# ModuleCarrier-NINA-B1-v1_0_0.net
KiCad netlist of a schematic drawn in EAGLE
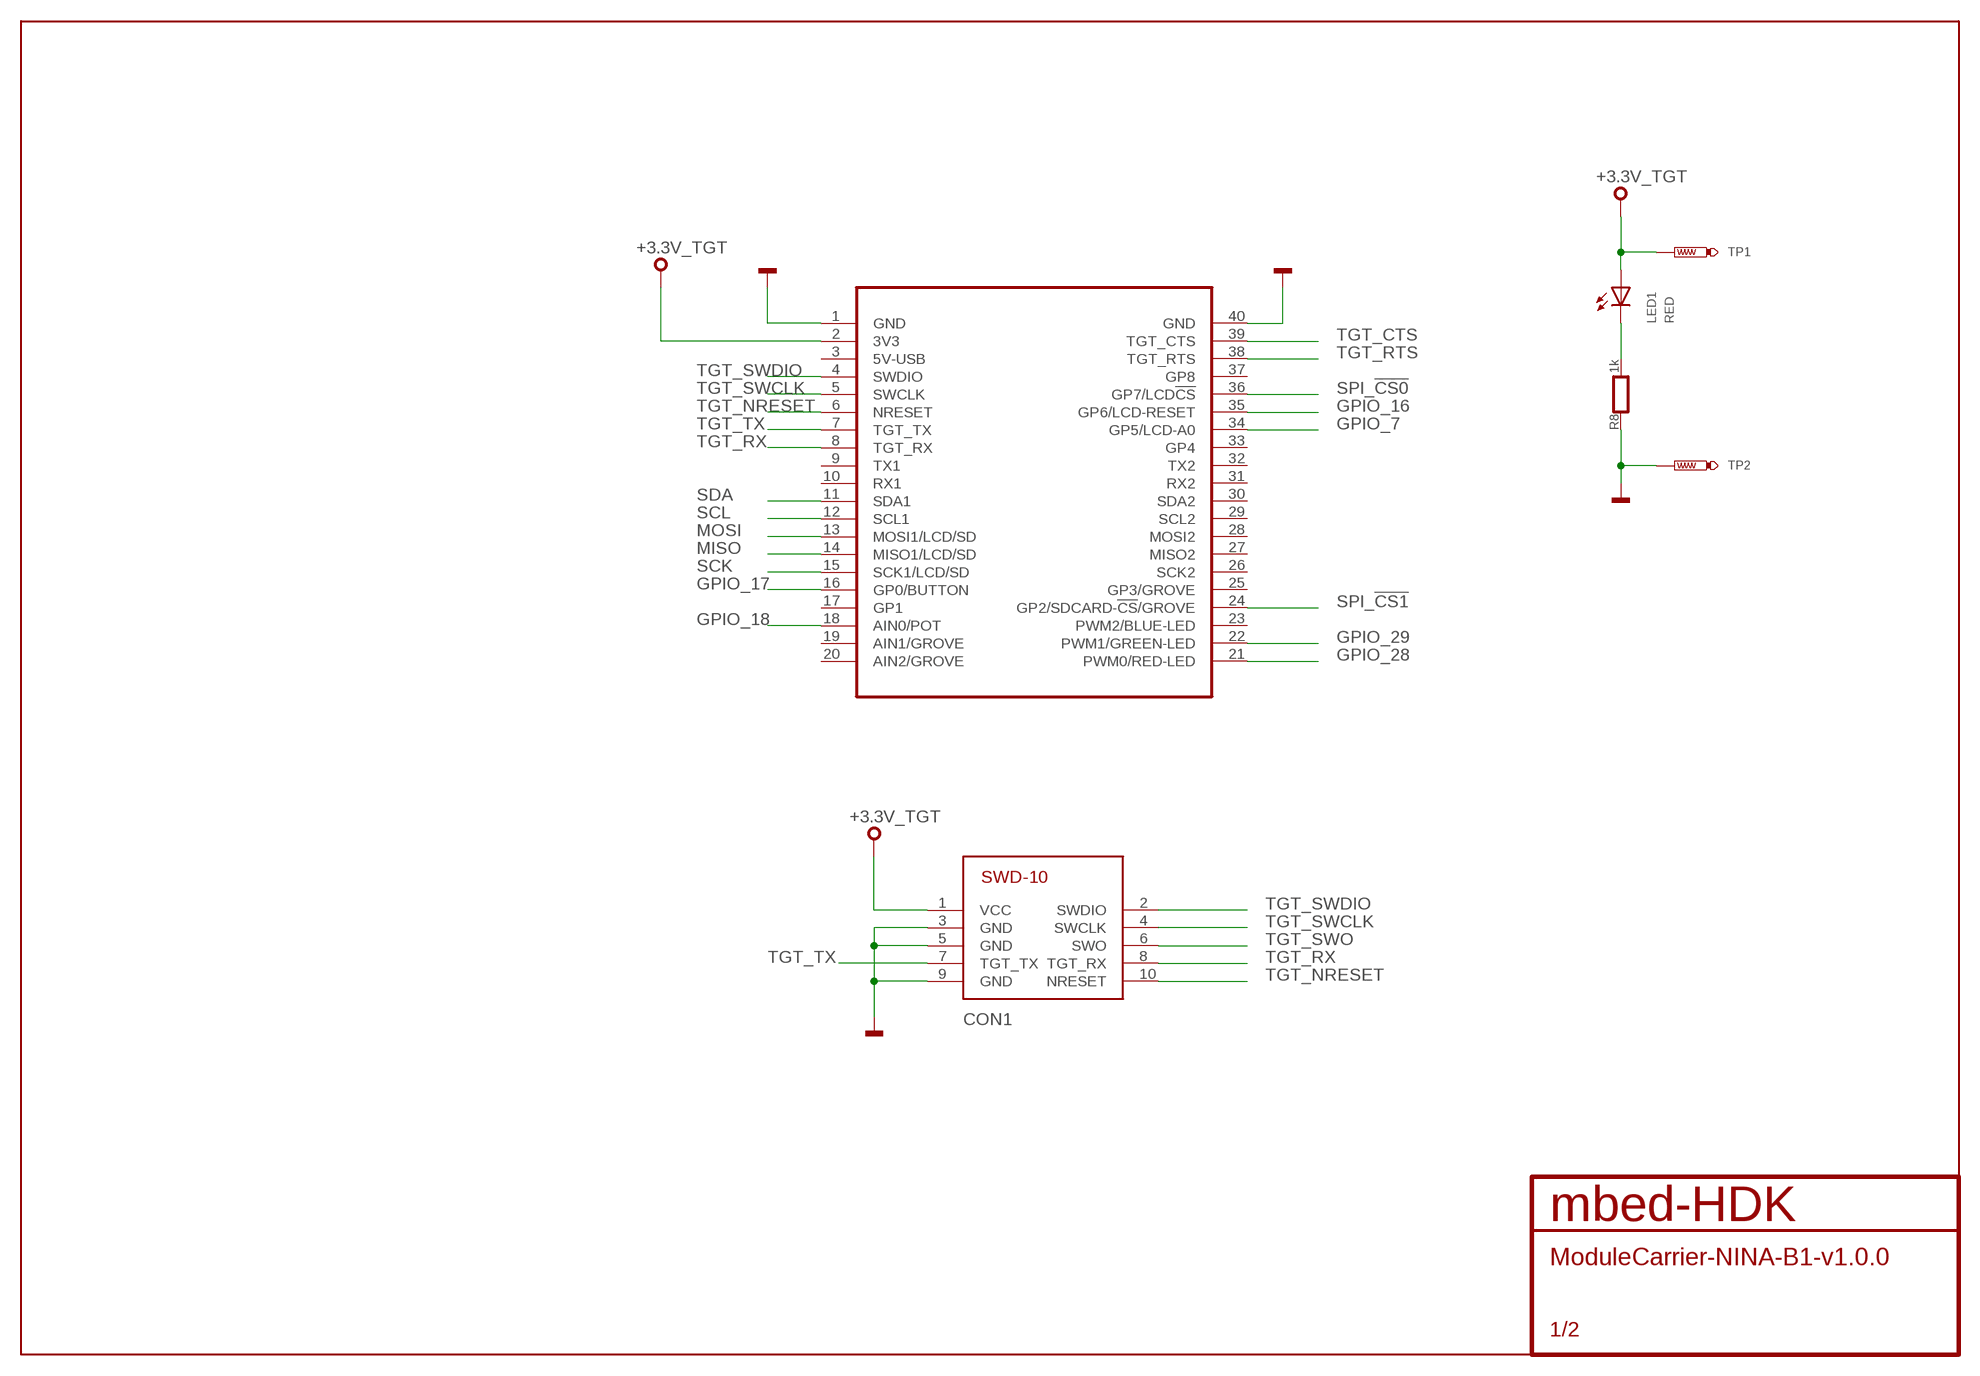
[diagram p0: schematic, sheet 1]
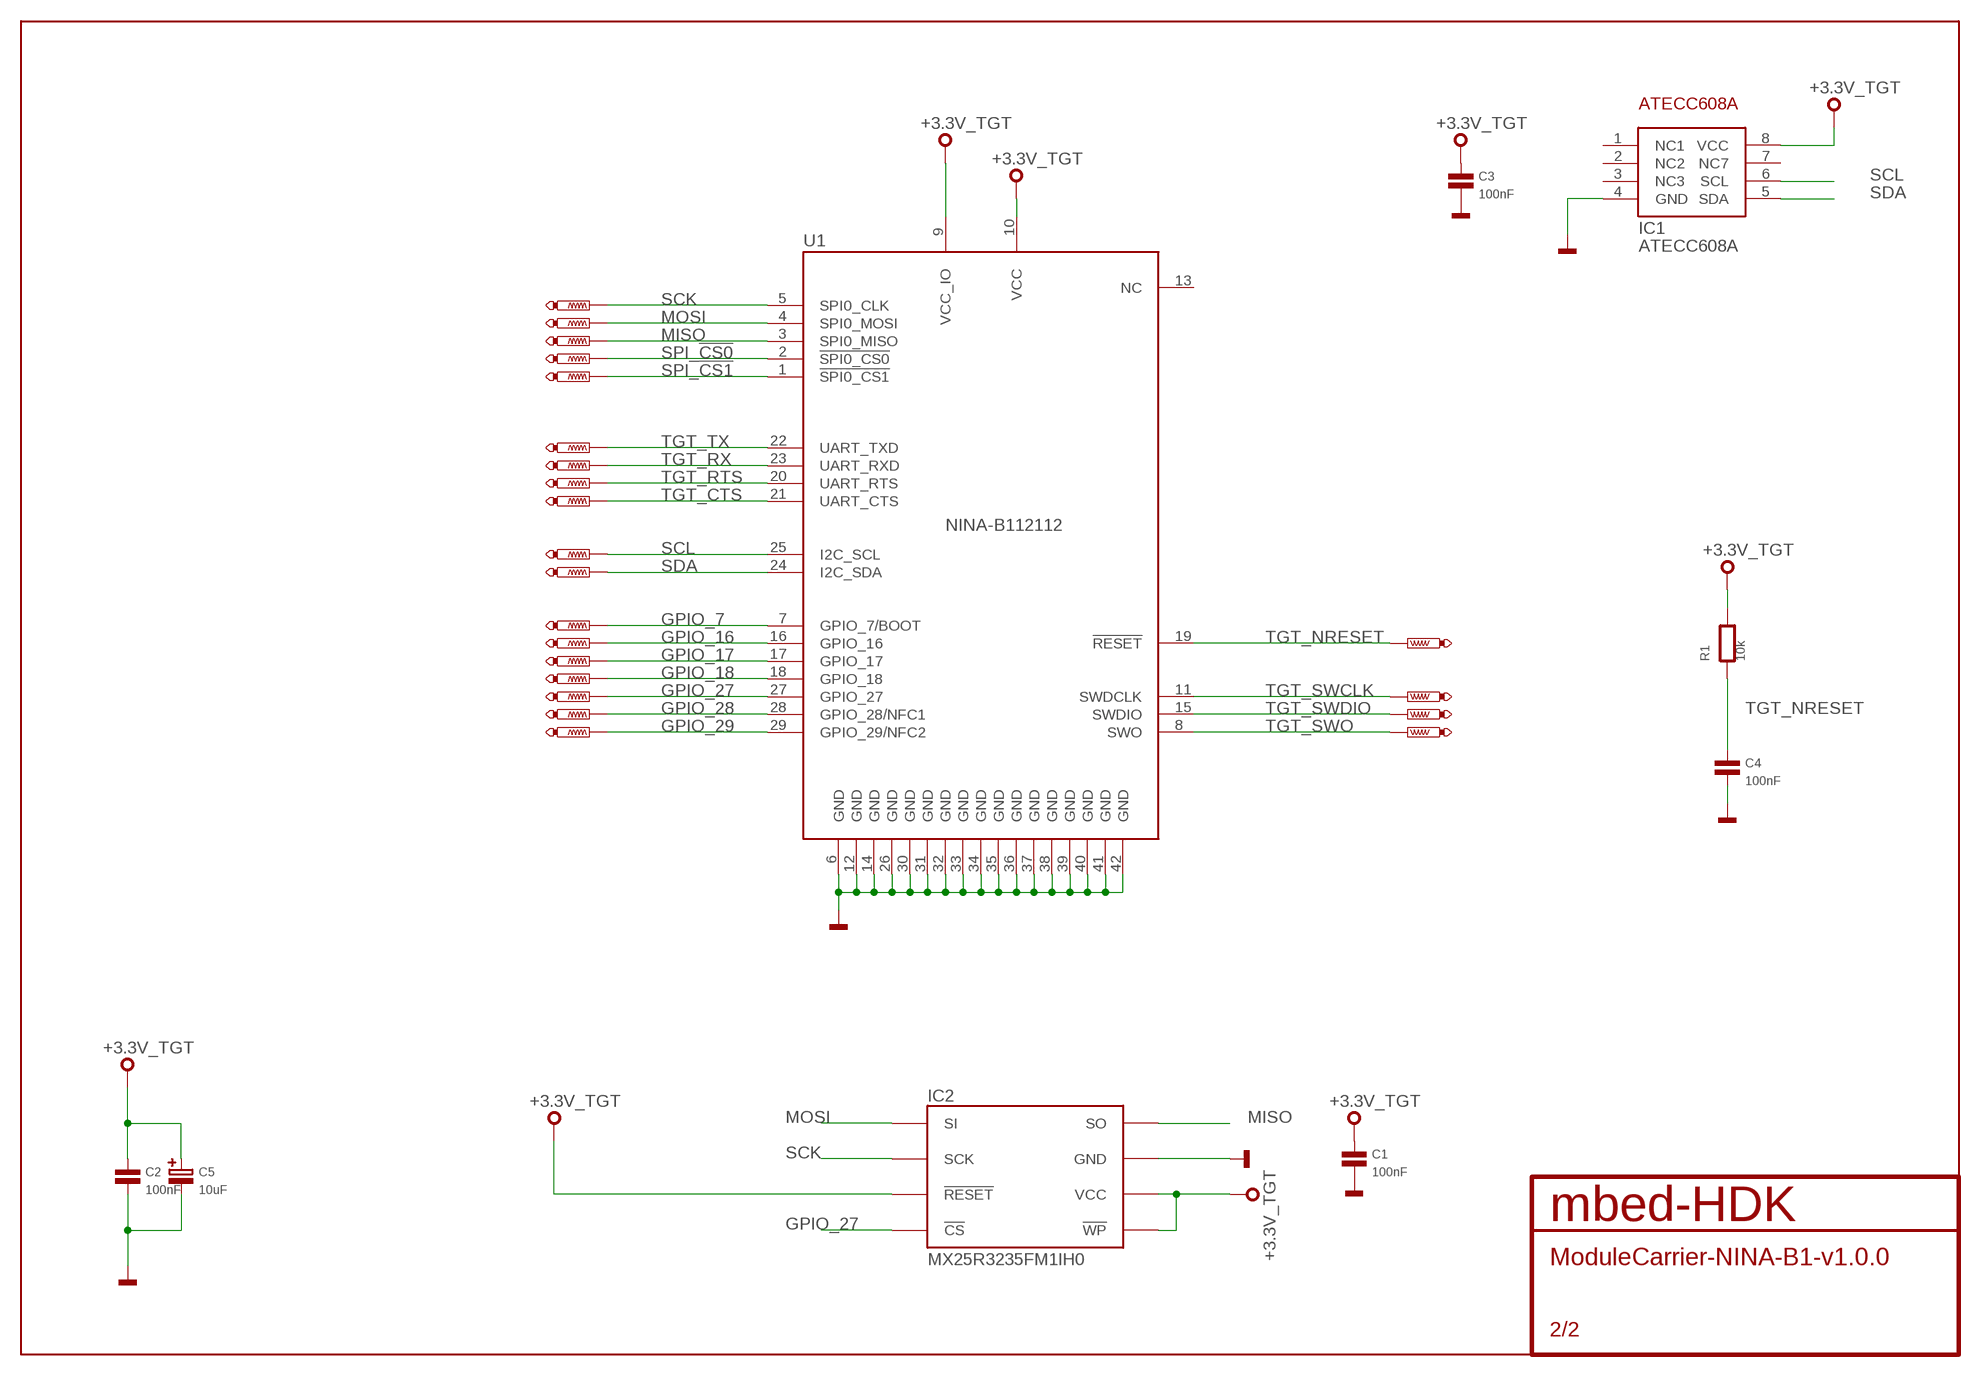
[diagram p1: schematic, sheet 2]

(export (version "E")
  (design (tool "Eeschema 10.0.6"))
  (components
    (comp (ref "C1")
      (value "100nF")
      (footprint "eagle-import:0603")
      (libsource (lib "eagle-import") (part "CAPACITOR0603"))
    )
    (comp (ref "C2")
      (value "100nF")
      (footprint "eagle-import:0603")
      (libsource (lib "eagle-import") (part "CAPACITOR0603"))
    )
    (comp (ref "C3")
      (value "100nF")
      (footprint "eagle-import:0603")
      (libsource (lib "eagle-import") (part "CAPACITOR0603"))
    )
    (comp (ref "C4")
      (value "100nF")
      (footprint "eagle-import:0603")
      (libsource (lib "eagle-import") (part "CAPACITOR0603"))
    )
    (comp (ref "C5")
      (value "10uF")
      (footprint "eagle-import:SMC_B")
      (fields (field (name "MF") "Kemet"))
      (libsource (lib "eagle-import") (part "CAPACITOR-POLARISEDB"))
    )
    (comp (ref "IC1")
      (value "ATECC608A")
      (footprint "eagle-import:SO8")
      (libsource (lib "eagle-import") (part "ATECC608A"))
    )
    (comp (ref "IC2")
      (value "MX25R3235FM1IH0")
      (footprint "eagle-import:SO8")
      (fields (field (name "MF") "Macronix"))
      (libsource (lib "eagle-import") (part "MX25R3235FM1IH0"))
    )
    (comp (ref "R1")
      (value "10k")
      (footprint "eagle-import:0603")
      (libsource (lib "eagle-import") (part "RESISTOR0603"))
    )
    (comp (ref "TP3")
      (value "PTR1B1,27")
      (footprint "eagle-import:B1,27")
      (libsource (lib "eagle-import") (part "PTR1B1,27"))
    )
    (comp (ref "TP4")
      (value "PTR1B1,27")
      (footprint "eagle-import:B1,27")
      (libsource (lib "eagle-import") (part "PTR1B1,27"))
    )
    (comp (ref "TP5")
      (value "PTR1B1,27")
      (footprint "eagle-import:B1,27")
      (libsource (lib "eagle-import") (part "PTR1B1,27"))
    )
    (comp (ref "TP6")
      (value "PTR1B1,27")
      (footprint "eagle-import:B1,27")
      (libsource (lib "eagle-import") (part "PTR1B1,27"))
    )
    (comp (ref "TP7")
      (value "PTR1B1,27")
      (footprint "eagle-import:B1,27")
      (libsource (lib "eagle-import") (part "PTR1B1,27"))
    )
    (comp (ref "TP8")
      (value "PTR1B1,27")
      (footprint "eagle-import:B1,27")
      (libsource (lib "eagle-import") (part "PTR1B1,27"))
    )
    (comp (ref "TP9")
      (value "PTR1B1,27")
      (footprint "eagle-import:B1,27")
      (libsource (lib "eagle-import") (part "PTR1B1,27"))
    )
    (comp (ref "TP10")
      (value "PTR1B1,27")
      (footprint "eagle-import:B1,27")
      (libsource (lib "eagle-import") (part "PTR1B1,27"))
    )
    (comp (ref "TP11")
      (value "PTR1B1,27")
      (footprint "eagle-import:B1,27")
      (libsource (lib "eagle-import") (part "PTR1B1,27"))
    )
    (comp (ref "TP12")
      (value "PTR1B1,27")
      (footprint "eagle-import:B1,27")
      (libsource (lib "eagle-import") (part "PTR1B1,27"))
    )
    (comp (ref "TP13")
      (value "PTR1B1,27")
      (footprint "eagle-import:B1,27")
      (libsource (lib "eagle-import") (part "PTR1B1,27"))
    )
    (comp (ref "TP14")
      (value "PTR1B1,27")
      (footprint "eagle-import:B1,27")
      (libsource (lib "eagle-import") (part "PTR1B1,27"))
    )
    (comp (ref "TP15")
      (value "PTR1B1,27")
      (footprint "eagle-import:B1,27")
      (libsource (lib "eagle-import") (part "PTR1B1,27"))
    )
    (comp (ref "TP16")
      (value "PTR1B1,27")
      (footprint "eagle-import:B1,27")
      (libsource (lib "eagle-import") (part "PTR1B1,27"))
    )
    (comp (ref "TP17")
      (value "PTR1B1,27")
      (footprint "eagle-import:B1,27")
      (libsource (lib "eagle-import") (part "PTR1B1,27"))
    )
    (comp (ref "TP18")
      (value "PTR1B1,27")
      (footprint "eagle-import:B1,27")
      (libsource (lib "eagle-import") (part "PTR1B1,27"))
    )
    (comp (ref "TP19")
      (value "PTR1B1,27")
      (footprint "eagle-import:B1,27")
      (libsource (lib "eagle-import") (part "PTR1B1,27"))
    )
    (comp (ref "TP20")
      (value "PTR1B1,27")
      (footprint "eagle-import:B1,27")
      (libsource (lib "eagle-import") (part "PTR1B1,27"))
    )
    (comp (ref "TP21")
      (value "PTR1B1,27")
      (footprint "eagle-import:B1,27")
      (libsource (lib "eagle-import") (part "PTR1B1,27"))
    )
    (comp (ref "TP22")
      (value "PTR1B1,27")
      (footprint "eagle-import:B1,27")
      (libsource (lib "eagle-import") (part "PTR1B1,27"))
    )
    (comp (ref "TP23")
      (value "PTR1B1,27")
      (footprint "eagle-import:B1,27")
      (libsource (lib "eagle-import") (part "PTR1B1,27"))
    )
    (comp (ref "TP24")
      (value "PTR1B1,27")
      (footprint "eagle-import:B1,27")
      (libsource (lib "eagle-import") (part "PTR1B1,27"))
    )
    (comp (ref "U1")
      (value "NINA-B112112")
      (footprint "eagle-import:NINA112-42")
      (libsource (lib "eagle-import") (part "NINA-B112112"))
    )
    (comp (ref "CON1")
      (value "SWD-10/TC2050_SMD")
      (footprint "eagle-import:FTSH-105-02")
      (libsource (lib "eagle-import") (part "SWD-10/TC2050_SMD"))
    )
    (comp (ref "LED1")
      (value "RED")
      (footprint "eagle-import:CHIPLED_0603")
      (fields (field (name "MF") "Wurth Electronics Inc"))
      (libsource (lib "eagle-import") (part "SMD_LED0603"))
    )
    (comp (ref "MOD1")
      (value "MODULE_DAUGHTER")
      (footprint "eagle-import:MODULE_DAUGHTER")
      (libsource (lib "eagle-import") (part "MODULE_DAUGHTER"))
    )
    (comp (ref "R8")
      (value "1k")
      (footprint "eagle-import:0603")
      (libsource (lib "eagle-import") (part "RESISTOR0603"))
    )
    (comp (ref "TP1")
      (value "TEST-POINT-50R-PTH")
      (footprint "eagle-import:TP50-PTH")
      (libsource (lib "eagle-import") (part "TEST-POINT-50R-PTH"))
    )
    (comp (ref "TP2")
      (value "TEST-POINT-50R-PTH")
      (footprint "eagle-import:TP50-PTH")
      (libsource (lib "eagle-import") (part "TEST-POINT-50R-PTH"))
    )
  )
  (nets
    (net (code "1") (name "+3.3V_TGT") (class "Default")
      (node (ref "C1") (pin "1") (pinfunction "P$1_1") (pintype "passive"))
      (node (ref "C2") (pin "1") (pinfunction "P$1_1") (pintype "passive"))
      (node (ref "C3") (pin "1") (pinfunction "P$1_1") (pintype "passive"))
      (node (ref "C5") (pin "+") (pinfunction "+_+") (pintype "passive"))
      (node (ref "CON1") (pin "1") (pinfunction "VCC_1") (pintype "bidirectional"))
      (node (ref "IC1") (pin "8") (pinfunction "VCC_8") (pintype "bidirectional"))
      (node (ref "IC2") (pin "3") (pinfunction "~{WP}_3") (pintype "bidirectional"))
      (node (ref "IC2") (pin "7") (pinfunction "~{RESET}_7") (pintype "bidirectional"))
      (node (ref "IC2") (pin "8") (pinfunction "VCC_8") (pintype "bidirectional"))
      (node (ref "LED1") (pin "A") (pinfunction "A_A") (pintype "passive"))
      (node (ref "MOD1") (pin "2") (pinfunction "3V3_2") (pintype "bidirectional"))
      (node (ref "R1") (pin "2") (pinfunction "P$2_2") (pintype "passive"))
      (node (ref "TP1") (pin "TP") (pinfunction "TP_TP") (pintype "input"))
      (node (ref "U1") (pin "10") (pinfunction "VCC_10") (pintype "power_in"))
      (node (ref "U1") (pin "9") (pinfunction "VCC_IO_9") (pintype "power_in"))
    )
    (net (code "2") (name "GND") (class "Default")
      (node (ref "C1") (pin "2") (pinfunction "P$2_2") (pintype "passive"))
      (node (ref "C2") (pin "2") (pinfunction "P$2_2") (pintype "passive"))
      (node (ref "C3") (pin "2") (pinfunction "P$2_2") (pintype "passive"))
      (node (ref "C4") (pin "2") (pinfunction "P$2_2") (pintype "passive"))
      (node (ref "C5") (pin "-") (pinfunction "-_-") (pintype "passive"))
      (node (ref "CON1") (pin "3") (pinfunction "GND_3") (pintype "bidirectional"))
      (node (ref "CON1") (pin "5") (pinfunction "GND_5") (pintype "bidirectional"))
      (node (ref "CON1") (pin "9") (pinfunction "GND_9") (pintype "bidirectional"))
      (node (ref "IC1") (pin "4") (pinfunction "GND_4") (pintype "bidirectional"))
      (node (ref "IC2") (pin "4") (pinfunction "GND_4") (pintype "bidirectional"))
      (node (ref "MOD1") (pin "1") (pinfunction "GND_1") (pintype "bidirectional"))
      (node (ref "MOD1") (pin "40") (pinfunction "GND_40") (pintype "bidirectional"))
      (node (ref "R8") (pin "1") (pinfunction "P$1_1") (pintype "passive"))
      (node (ref "TP2") (pin "TP") (pinfunction "TP_TP") (pintype "input"))
      (node (ref "U1") (pin "12") (pinfunction "GND_12") (pintype "power_in"))
      (node (ref "U1") (pin "14") (pinfunction "GND_14") (pintype "power_in"))
      (node (ref "U1") (pin "26") (pinfunction "GND_26") (pintype "power_in"))
      (node (ref "U1") (pin "30") (pinfunction "GND_30") (pintype "power_in"))
      (node (ref "U1") (pin "31") (pinfunction "GND_31") (pintype "power_in"))
      (node (ref "U1") (pin "32") (pinfunction "GND_32") (pintype "power_in"))
      (node (ref "U1") (pin "33") (pinfunction "GND_33") (pintype "power_in"))
      (node (ref "U1") (pin "34") (pinfunction "GND_34") (pintype "power_in"))
      (node (ref "U1") (pin "35") (pinfunction "GND_35") (pintype "power_in"))
      (node (ref "U1") (pin "36") (pinfunction "GND_36") (pintype "power_in"))
      (node (ref "U1") (pin "37") (pinfunction "GND_37") (pintype "power_in"))
      (node (ref "U1") (pin "38") (pinfunction "GND_38") (pintype "power_in"))
      (node (ref "U1") (pin "39") (pinfunction "GND_39") (pintype "power_in"))
      (node (ref "U1") (pin "40") (pinfunction "GND_40") (pintype "power_in"))
      (node (ref "U1") (pin "41") (pinfunction "GND_41") (pintype "power_in"))
      (node (ref "U1") (pin "42") (pinfunction "GND_42") (pintype "power_in"))
      (node (ref "U1") (pin "6") (pinfunction "GND_6") (pintype "power_in"))
    )
    (net (code "3") (name "GPIO_7") (class "Default")
      (node (ref "MOD1") (pin "34") (pinfunction "GP5/LCD-A0_34") (pintype "bidirectional"))
      (node (ref "TP14") (pin "TP") (pinfunction "TP_TP") (pintype "input"))
      (node (ref "U1") (pin "7") (pinfunction "GPIO_7/BOOT_7") (pintype "bidirectional"))
    )
    (net (code "4") (name "GPIO_16") (class "Default")
      (node (ref "MOD1") (pin "35") (pinfunction "GP6/LCD-RESET_35") (pintype "bidirectional"))
      (node (ref "TP15") (pin "TP") (pinfunction "TP_TP") (pintype "input"))
      (node (ref "U1") (pin "16") (pinfunction "GPIO_16_16") (pintype "bidirectional"))
    )
    (net (code "5") (name "GPIO_17") (class "Default")
      (node (ref "MOD1") (pin "16") (pinfunction "GP0/BUTTON_16") (pintype "bidirectional"))
      (node (ref "TP16") (pin "TP") (pinfunction "TP_TP") (pintype "input"))
      (node (ref "U1") (pin "17") (pinfunction "GPIO_17_17") (pintype "bidirectional"))
    )
    (net (code "6") (name "GPIO_18") (class "Default")
      (node (ref "MOD1") (pin "18") (pinfunction "AIN0/POT_18") (pintype "bidirectional"))
      (node (ref "TP17") (pin "TP") (pinfunction "TP_TP") (pintype "input"))
      (node (ref "U1") (pin "18") (pinfunction "GPIO_18_18") (pintype "bidirectional"))
    )
    (net (code "7") (name "GPIO_27") (class "Default")
      (node (ref "IC2") (pin "1") (pinfunction "~{CS}_1") (pintype "bidirectional"))
      (node (ref "TP18") (pin "TP") (pinfunction "TP_TP") (pintype "input"))
      (node (ref "U1") (pin "27") (pinfunction "GPIO_27_27") (pintype "bidirectional"))
    )
    (net (code "8") (name "GPIO_28") (class "Default")
      (node (ref "MOD1") (pin "21") (pinfunction "PWM0/RED-LED_21") (pintype "bidirectional"))
      (node (ref "TP19") (pin "TP") (pinfunction "TP_TP") (pintype "input"))
      (node (ref "U1") (pin "28") (pinfunction "GPIO_28/NFC1_28") (pintype "bidirectional"))
    )
    (net (code "9") (name "GPIO_29") (class "Default")
      (node (ref "MOD1") (pin "22") (pinfunction "PWM1/GREEN-LED_22") (pintype "bidirectional"))
      (node (ref "TP20") (pin "TP") (pinfunction "TP_TP") (pintype "input"))
      (node (ref "U1") (pin "29") (pinfunction "GPIO_29/NFC2_29") (pintype "bidirectional"))
    )
    (net (code "10") (name "MISO") (class "Default")
      (node (ref "IC2") (pin "2") (pinfunction "SO_2") (pintype "bidirectional"))
      (node (ref "MOD1") (pin "14") (pinfunction "MISO1/LCD/SD_14") (pintype "bidirectional"))
      (node (ref "TP5") (pin "TP") (pinfunction "TP_TP") (pintype "input"))
      (node (ref "U1") (pin "3") (pinfunction "SPI0_MISO_3") (pintype "bidirectional"))
    )
    (net (code "11") (name "MOSI") (class "Default")
      (node (ref "IC2") (pin "5") (pinfunction "SI_5") (pintype "bidirectional"))
      (node (ref "MOD1") (pin "13") (pinfunction "MOSI1/LCD/SD_13") (pintype "bidirectional"))
      (node (ref "TP4") (pin "TP") (pinfunction "TP_TP") (pintype "input"))
      (node (ref "U1") (pin "4") (pinfunction "SPI0_MOSI_4") (pintype "bidirectional"))
    )
    (net (code "12") (name "Net-(R8-P$2)") (class "Default")
      (node (ref "LED1") (pin "C") (pinfunction "C_C") (pintype "passive"))
      (node (ref "R8") (pin "2") (pinfunction "P$2_2") (pintype "passive"))
    )
    (net (code "13") (name "SCK") (class "Default")
      (node (ref "IC2") (pin "6") (pinfunction "SCK_6") (pintype "bidirectional"))
      (node (ref "MOD1") (pin "15") (pinfunction "SCK1/LCD/SD_15") (pintype "bidirectional"))
      (node (ref "TP3") (pin "TP") (pinfunction "TP_TP") (pintype "input"))
      (node (ref "U1") (pin "5") (pinfunction "SPI0_CLK_5") (pintype "bidirectional"))
    )
    (net (code "14") (name "SCL") (class "Default")
      (node (ref "IC1") (pin "6") (pinfunction "SCL_6") (pintype "bidirectional"))
      (node (ref "MOD1") (pin "12") (pinfunction "SCL1_12") (pintype "bidirectional"))
      (node (ref "TP12") (pin "TP") (pinfunction "TP_TP") (pintype "input"))
      (node (ref "U1") (pin "25") (pinfunction "I2C_SCL_25") (pintype "bidirectional"))
    )
    (net (code "15") (name "SDA") (class "Default")
      (node (ref "IC1") (pin "5") (pinfunction "SDA_5") (pintype "bidirectional"))
      (node (ref "MOD1") (pin "11") (pinfunction "SDA1_11") (pintype "bidirectional"))
      (node (ref "TP13") (pin "TP") (pinfunction "TP_TP") (pintype "input"))
      (node (ref "U1") (pin "24") (pinfunction "I2C_SDA_24") (pintype "bidirectional"))
    )
    (net (code "16") (name "SPI_~{CS0}") (class "Default")
      (node (ref "MOD1") (pin "36") (pinfunction "GP7/LCD~{CS}_36") (pintype "bidirectional"))
      (node (ref "TP6") (pin "TP") (pinfunction "TP_TP") (pintype "input"))
      (node (ref "U1") (pin "2") (pinfunction "~{SPI0_CS0}_2") (pintype "bidirectional"))
    )
    (net (code "17") (name "SPI_~{CS1}") (class "Default")
      (node (ref "MOD1") (pin "24") (pinfunction "GP2/SDCARD-~{CS}/GROVE_24") (pintype "bidirectional"))
      (node (ref "TP7") (pin "TP") (pinfunction "TP_TP") (pintype "input"))
      (node (ref "U1") (pin "1") (pinfunction "~{SPI0_CS1}_1") (pintype "output"))
    )
    (net (code "18") (name "TGT_CTS") (class "Default")
      (node (ref "MOD1") (pin "39") (pinfunction "TGT_CTS_39") (pintype "bidirectional"))
      (node (ref "TP11") (pin "TP") (pinfunction "TP_TP") (pintype "input"))
      (node (ref "U1") (pin "21") (pinfunction "UART_CTS_21") (pintype "bidirectional"))
    )
    (net (code "19") (name "TGT_NRESET") (class "Default")
      (node (ref "C4") (pin "1") (pinfunction "P$1_1") (pintype "passive"))
      (node (ref "CON1") (pin "10") (pinfunction "NRESET_10") (pintype "bidirectional"))
      (node (ref "MOD1") (pin "6") (pinfunction "NRESET_6") (pintype "bidirectional"))
      (node (ref "R1") (pin "1") (pinfunction "P$1_1") (pintype "passive"))
      (node (ref "TP21") (pin "TP") (pinfunction "TP_TP") (pintype "input"))
      (node (ref "U1") (pin "19") (pinfunction "~{RESET}_19") (pintype "input"))
    )
    (net (code "20") (name "TGT_RTS") (class "Default")
      (node (ref "MOD1") (pin "38") (pinfunction "TGT_RTS_38") (pintype "bidirectional"))
      (node (ref "TP10") (pin "TP") (pinfunction "TP_TP") (pintype "input"))
      (node (ref "U1") (pin "20") (pinfunction "UART_RTS_20") (pintype "bidirectional"))
    )
    (net (code "21") (name "TGT_RX") (class "Default")
      (node (ref "CON1") (pin "8") (pinfunction "TGT_RX_8") (pintype "bidirectional"))
      (node (ref "MOD1") (pin "8") (pinfunction "TGT_RX_8") (pintype "bidirectional"))
      (node (ref "TP9") (pin "TP") (pinfunction "TP_TP") (pintype "input"))
      (node (ref "U1") (pin "23") (pinfunction "UART_RXD_23") (pintype "bidirectional"))
    )
    (net (code "22") (name "TGT_SWCLK") (class "Default")
      (node (ref "CON1") (pin "4") (pinfunction "SWCLK_4") (pintype "bidirectional"))
      (node (ref "MOD1") (pin "5") (pinfunction "SWCLK_5") (pintype "bidirectional"))
      (node (ref "TP22") (pin "TP") (pinfunction "TP_TP") (pintype "input"))
      (node (ref "U1") (pin "11") (pinfunction "SWDCLK_11") (pintype "input"))
    )
    (net (code "23") (name "TGT_SWDIO") (class "Default")
      (node (ref "CON1") (pin "2") (pinfunction "SWDIO_2") (pintype "bidirectional"))
      (node (ref "MOD1") (pin "4") (pinfunction "SWDIO_4") (pintype "bidirectional"))
      (node (ref "TP23") (pin "TP") (pinfunction "TP_TP") (pintype "input"))
      (node (ref "U1") (pin "15") (pinfunction "SWDIO_15") (pintype "bidirectional"))
    )
    (net (code "24") (name "TGT_SWO") (class "Default")
      (node (ref "CON1") (pin "6") (pinfunction "SWO_6") (pintype "bidirectional"))
      (node (ref "TP24") (pin "TP") (pinfunction "TP_TP") (pintype "input"))
      (node (ref "U1") (pin "8") (pinfunction "SWO_8") (pintype "output"))
    )
    (net (code "25") (name "TGT_TX") (class "Default")
      (node (ref "CON1") (pin "7") (pinfunction "TGT_TX_7") (pintype "bidirectional"))
      (node (ref "MOD1") (pin "7") (pinfunction "TGT_TX_7") (pintype "bidirectional"))
      (node (ref "TP8") (pin "TP") (pinfunction "TP_TP") (pintype "input"))
      (node (ref "U1") (pin "22") (pinfunction "UART_TXD_22") (pintype "bidirectional"))
    )
    (net (code "26") (name "unconnected-(IC1-NC1-Pad1)") (class "Default")
      (node (ref "IC1") (pin "1") (pinfunction "NC1_1") (pintype "bidirectional"))
    )
    (net (code "27") (name "unconnected-(IC1-NC2-Pad2)") (class "Default")
      (node (ref "IC1") (pin "2") (pinfunction "NC2_2") (pintype "bidirectional"))
    )
    (net (code "28") (name "unconnected-(IC1-NC3-Pad3)") (class "Default")
      (node (ref "IC1") (pin "3") (pinfunction "NC3_3") (pintype "bidirectional"))
    )
    (net (code "29") (name "unconnected-(IC1-NC7-Pad7)") (class "Default")
      (node (ref "IC1") (pin "7") (pinfunction "NC7_7") (pintype "bidirectional"))
    )
    (net (code "30") (name "unconnected-(MOD1-5V-USB-Pad3)") (class "Default")
      (node (ref "MOD1") (pin "3") (pinfunction "5V-USB_3") (pintype "bidirectional"))
    )
    (net (code "31") (name "unconnected-(MOD1-AIN1{slash}GROVE-Pad19)") (class "Default")
      (node (ref "MOD1") (pin "19") (pinfunction "AIN1/GROVE_19") (pintype "bidirectional"))
    )
    (net (code "32") (name "unconnected-(MOD1-AIN2{slash}GROVE-Pad20)") (class "Default")
      (node (ref "MOD1") (pin "20") (pinfunction "AIN2/GROVE_20") (pintype "bidirectional"))
    )
    (net (code "33") (name "unconnected-(MOD1-GP1-Pad17)") (class "Default")
      (node (ref "MOD1") (pin "17") (pinfunction "GP1_17") (pintype "bidirectional"))
    )
    (net (code "34") (name "unconnected-(MOD1-GP3{slash}GROVE-Pad25)") (class "Default")
      (node (ref "MOD1") (pin "25") (pinfunction "GP3/GROVE_25") (pintype "bidirectional"))
    )
    (net (code "35") (name "unconnected-(MOD1-GP4-Pad33)") (class "Default")
      (node (ref "MOD1") (pin "33") (pinfunction "GP4_33") (pintype "bidirectional"))
    )
    (net (code "36") (name "unconnected-(MOD1-GP8-Pad37)") (class "Default")
      (node (ref "MOD1") (pin "37") (pinfunction "GP8_37") (pintype "bidirectional"))
    )
    (net (code "37") (name "unconnected-(MOD1-MISO2-Pad27)") (class "Default")
      (node (ref "MOD1") (pin "27") (pinfunction "MISO2_27") (pintype "bidirectional"))
    )
    (net (code "38") (name "unconnected-(MOD1-MOSI2-Pad28)") (class "Default")
      (node (ref "MOD1") (pin "28") (pinfunction "MOSI2_28") (pintype "bidirectional"))
    )
    (net (code "39") (name "unconnected-(MOD1-PWM2{slash}BLUE-LED-Pad23)") (class "Default")
      (node (ref "MOD1") (pin "23") (pinfunction "PWM2/BLUE-LED_23") (pintype "bidirectional"))
    )
    (net (code "40") (name "unconnected-(MOD1-RX1-Pad10)") (class "Default")
      (node (ref "MOD1") (pin "10") (pinfunction "RX1_10") (pintype "bidirectional"))
    )
    (net (code "41") (name "unconnected-(MOD1-RX2-Pad31)") (class "Default")
      (node (ref "MOD1") (pin "31") (pinfunction "RX2_31") (pintype "bidirectional"))
    )
    (net (code "42") (name "unconnected-(MOD1-SCK2-Pad26)") (class "Default")
      (node (ref "MOD1") (pin "26") (pinfunction "SCK2_26") (pintype "bidirectional"))
    )
    (net (code "43") (name "unconnected-(MOD1-SCL2-Pad29)") (class "Default")
      (node (ref "MOD1") (pin "29") (pinfunction "SCL2_29") (pintype "bidirectional"))
    )
    (net (code "44") (name "unconnected-(MOD1-SDA2-Pad30)") (class "Default")
      (node (ref "MOD1") (pin "30") (pinfunction "SDA2_30") (pintype "bidirectional"))
    )
    (net (code "45") (name "unconnected-(MOD1-TX1-Pad9)") (class "Default")
      (node (ref "MOD1") (pin "9") (pinfunction "TX1_9") (pintype "bidirectional"))
    )
    (net (code "46") (name "unconnected-(MOD1-TX2-Pad32)") (class "Default")
      (node (ref "MOD1") (pin "32") (pinfunction "TX2_32") (pintype "bidirectional"))
    )
    (net (code "47") (name "unconnected-(U1-NC-Pad13)") (class "Default")
      (node (ref "U1") (pin "13") (pinfunction "NC_13") (pintype "no_connect"))
    )
  )
)
